# IOTPanel.net
KiCad netlist of a schematic drawn in EAGLE
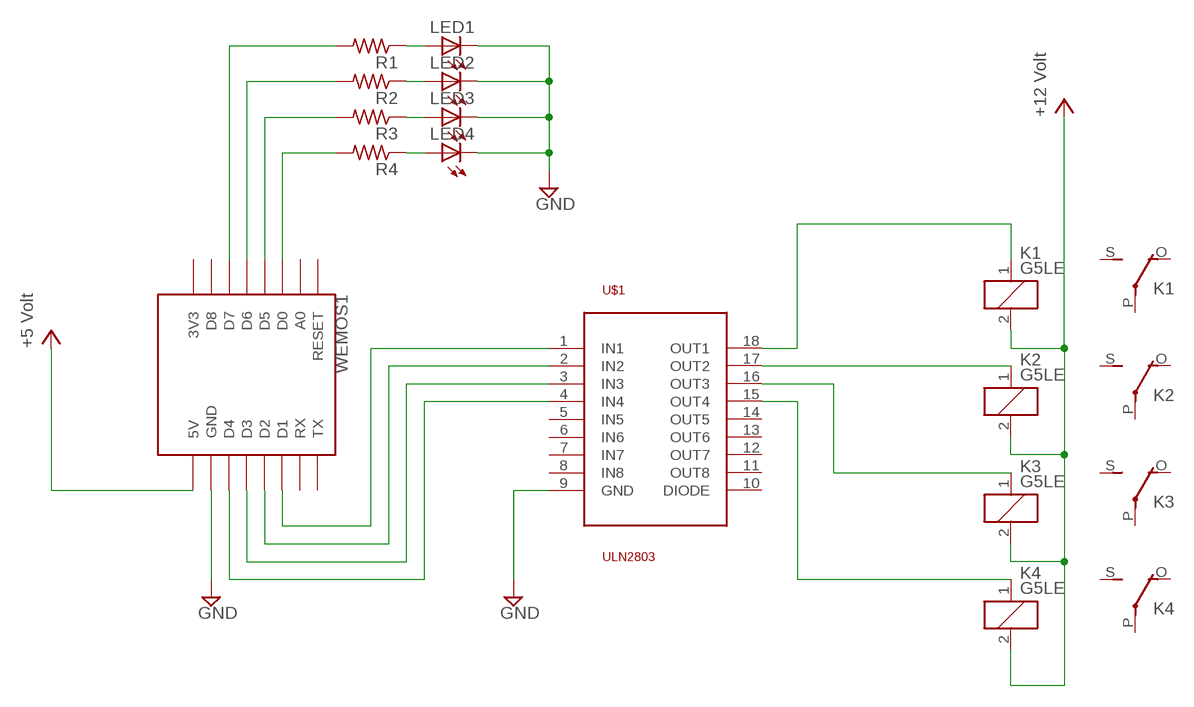
[diagram p0: schematic, sheet 1]

(export (version "E")
  (design (tool "Eeschema 10.0.6"))
  (components
    (comp (ref "K1")
      (value "G5LE")
      (footprint "eagle-import:G5LE")
      (libsource (lib "eagle-import") (part "G5LE"))
    )
    (comp (ref "K2")
      (value "G5LE")
      (footprint "eagle-import:G5LE")
      (libsource (lib "eagle-import") (part "G5LE"))
    )
    (comp (ref "K3")
      (value "G5LE")
      (footprint "eagle-import:G5LE")
      (libsource (lib "eagle-import") (part "G5LE"))
    )
    (comp (ref "K4")
      (value "G5LE")
      (footprint "eagle-import:G5LE")
      (libsource (lib "eagle-import") (part "G5LE"))
    )
    (comp (ref "LED1")
      (value "LED")
      (footprint "eagle-import:SMARTLED-TTW")
      (libsource (lib "eagle-import") (part "LED"))
    )
    (comp (ref "LED2")
      (value "LED")
      (footprint "eagle-import:SMARTLED-TTW")
      (libsource (lib "eagle-import") (part "LED"))
    )
    (comp (ref "LED3")
      (value "LED")
      (footprint "eagle-import:SMARTLED-TTW")
      (libsource (lib "eagle-import") (part "LED"))
    )
    (comp (ref "LED4")
      (value "LED")
      (footprint "eagle-import:SMARTLED-TTW")
      (libsource (lib "eagle-import") (part "LED"))
    )
    (comp (ref "R1")
      (value "R-US_0204/2V")
      (footprint "eagle-import:0204V")
      (libsource (lib "eagle-import") (part "R-US_0204/2V"))
    )
    (comp (ref "R2")
      (value "R-US_0204/2V")
      (footprint "eagle-import:0204V")
      (libsource (lib "eagle-import") (part "R-US_0204/2V"))
    )
    (comp (ref "R3")
      (value "R-US_0204/2V")
      (footprint "eagle-import:0204V")
      (libsource (lib "eagle-import") (part "R-US_0204/2V"))
    )
    (comp (ref "R4")
      (value "R-US_0204/2V")
      (footprint "eagle-import:0204V")
      (libsource (lib "eagle-import") (part "R-US_0204/2V"))
    )
    (comp (ref "U$1")
      (value "ULN2803")
      (footprint "eagle-import:SO18L")
      (libsource (lib "eagle-import") (part "ULN2803"))
    )
    (comp (ref "WEMOS1")
      (value "WEMOS-D1-MINI")
      (footprint "eagle-import:WEMOS-D1-MINI")
      (libsource (lib "eagle-import") (part "WEMOS-D1-MINI"))
    )
  )
  (nets
    (net (code "1") (name "+12 Volt") (class "Default")
      (node (ref "K1") (pin "2") (pinfunction "2_2") (pintype "passive"))
      (node (ref "K2") (pin "2") (pinfunction "2_2") (pintype "passive"))
      (node (ref "K3") (pin "2") (pinfunction "2_2") (pintype "passive"))
      (node (ref "K4") (pin "2") (pinfunction "2_2") (pintype "passive"))
      (node (ref "WEMOS1") (pin "5V") (pinfunction "5V_5V") (pintype "bidirectional"))
    )
    (net (code "2") (name "/DIODE") (class "Default")
      (node (ref "U$1") (pin "10") (pinfunction "DIODE_10") (pintype "power_in"))
    )
    (net (code "3") (name "GND") (class "Default")
      (node (ref "LED1") (pin "C@1") (pinfunction "C_C@1") (pintype "passive"))
      (node (ref "LED2") (pin "C@1") (pinfunction "C_C@1") (pintype "passive"))
      (node (ref "LED3") (pin "C@1") (pinfunction "C_C@1") (pintype "passive"))
      (node (ref "LED4") (pin "C@1") (pinfunction "C_C@1") (pintype "passive"))
      (node (ref "U$1") (pin "9") (pinfunction "GND_9") (pintype "power_in"))
      (node (ref "WEMOS1") (pin "GND") (pinfunction "GND_GND") (pintype "bidirectional"))
    )
    (net (code "4") (name "Net-(LED1-A)") (class "Default")
      (node (ref "LED1") (pin "A@1") (pinfunction "A_A@1") (pintype "passive"))
      (node (ref "R1") (pin "1") (pinfunction "1_1") (pintype "passive"))
    )
    (net (code "5") (name "Net-(LED2-A)") (class "Default")
      (node (ref "LED2") (pin "A@1") (pinfunction "A_A@1") (pintype "passive"))
      (node (ref "R2") (pin "1") (pinfunction "1_1") (pintype "passive"))
    )
    (net (code "6") (name "Net-(LED3-A)") (class "Default")
      (node (ref "LED3") (pin "A@1") (pinfunction "A_A@1") (pintype "passive"))
      (node (ref "R3") (pin "1") (pinfunction "1_1") (pintype "passive"))
    )
    (net (code "7") (name "Net-(LED4-A)") (class "Default")
      (node (ref "LED4") (pin "A@1") (pinfunction "A_A@1") (pintype "passive"))
      (node (ref "R4") (pin "1") (pinfunction "1_1") (pintype "passive"))
    )
    (net (code "8") (name "Net-(R1-Pad2)") (class "Default")
      (node (ref "R1") (pin "2") (pinfunction "2_2") (pintype "passive"))
      (node (ref "WEMOS1") (pin "D7") (pinfunction "D7_D7") (pintype "bidirectional"))
    )
    (net (code "9") (name "Net-(R2-Pad2)") (class "Default")
      (node (ref "R2") (pin "2") (pinfunction "2_2") (pintype "passive"))
      (node (ref "WEMOS1") (pin "D6") (pinfunction "D6_D6") (pintype "bidirectional"))
    )
    (net (code "10") (name "Net-(R3-Pad2)") (class "Default")
      (node (ref "R3") (pin "2") (pinfunction "2_2") (pintype "passive"))
      (node (ref "WEMOS1") (pin "D5") (pinfunction "D5_D5") (pintype "bidirectional"))
    )
    (net (code "11") (name "Net-(R4-Pad2)") (class "Default")
      (node (ref "R4") (pin "2") (pinfunction "2_2") (pintype "passive"))
      (node (ref "WEMOS1") (pin "D0") (pinfunction "D0_D0") (pintype "bidirectional"))
    )
    (net (code "12") (name "Net-(U$1-IN1)") (class "Default")
      (node (ref "U$1") (pin "1") (pinfunction "IN1_1") (pintype "input"))
      (node (ref "WEMOS1") (pin "D1") (pinfunction "D1_D1") (pintype "bidirectional"))
    )
    (net (code "13") (name "Net-(U$1-IN2)") (class "Default")
      (node (ref "U$1") (pin "2") (pinfunction "IN2_2") (pintype "input"))
      (node (ref "WEMOS1") (pin "D2") (pinfunction "D2_D2") (pintype "bidirectional"))
    )
    (net (code "14") (name "Net-(U$1-IN3)") (class "Default")
      (node (ref "U$1") (pin "3") (pinfunction "IN3_3") (pintype "input"))
      (node (ref "WEMOS1") (pin "D3") (pinfunction "D3_D3") (pintype "bidirectional"))
    )
    (net (code "15") (name "Net-(U$1-IN4)") (class "Default")
      (node (ref "U$1") (pin "4") (pinfunction "IN4_4") (pintype "input"))
      (node (ref "WEMOS1") (pin "D4") (pinfunction "D4_D4") (pintype "bidirectional"))
    )
    (net (code "16") (name "Net-(U$1-OUT1)") (class "Default")
      (node (ref "K1") (pin "1") (pinfunction "1_1") (pintype "passive"))
      (node (ref "U$1") (pin "18") (pinfunction "OUT1_18") (pintype "open_collector"))
    )
    (net (code "17") (name "Net-(U$1-OUT2)") (class "Default")
      (node (ref "K2") (pin "1") (pinfunction "1_1") (pintype "passive"))
      (node (ref "U$1") (pin "17") (pinfunction "OUT2_17") (pintype "open_collector"))
    )
    (net (code "18") (name "Net-(U$1-OUT3)") (class "Default")
      (node (ref "K3") (pin "1") (pinfunction "1_1") (pintype "passive"))
      (node (ref "U$1") (pin "16") (pinfunction "OUT3_16") (pintype "open_collector"))
    )
    (net (code "19") (name "Net-(U$1-OUT4)") (class "Default")
      (node (ref "K4") (pin "1") (pinfunction "1_1") (pintype "passive"))
      (node (ref "U$1") (pin "15") (pinfunction "OUT4_15") (pintype "open_collector"))
    )
    (net (code "20") (name "unconnected-(K1-PadO)") (class "Default")
      (node (ref "K1") (pin "O") (pinfunction "O_O") (pintype "passive"))
    )
    (net (code "21") (name "unconnected-(K1-PadP)") (class "Default")
      (node (ref "K1") (pin "P") (pinfunction "P_P") (pintype "passive"))
    )
    (net (code "22") (name "unconnected-(K1-PadS)") (class "Default")
      (node (ref "K1") (pin "S") (pinfunction "S_S") (pintype "passive"))
    )
    (net (code "23") (name "unconnected-(K2-PadO)") (class "Default")
      (node (ref "K2") (pin "O") (pinfunction "O_O") (pintype "passive"))
    )
    (net (code "24") (name "unconnected-(K2-PadP)") (class "Default")
      (node (ref "K2") (pin "P") (pinfunction "P_P") (pintype "passive"))
    )
    (net (code "25") (name "unconnected-(K2-PadS)") (class "Default")
      (node (ref "K2") (pin "S") (pinfunction "S_S") (pintype "passive"))
    )
    (net (code "26") (name "unconnected-(K3-PadO)") (class "Default")
      (node (ref "K3") (pin "O") (pinfunction "O_O") (pintype "passive"))
    )
    (net (code "27") (name "unconnected-(K3-PadP)") (class "Default")
      (node (ref "K3") (pin "P") (pinfunction "P_P") (pintype "passive"))
    )
    (net (code "28") (name "unconnected-(K3-PadS)") (class "Default")
      (node (ref "K3") (pin "S") (pinfunction "S_S") (pintype "passive"))
    )
    (net (code "29") (name "unconnected-(K4-PadO)") (class "Default")
      (node (ref "K4") (pin "O") (pinfunction "O_O") (pintype "passive"))
    )
    (net (code "30") (name "unconnected-(K4-PadP)") (class "Default")
      (node (ref "K4") (pin "P") (pinfunction "P_P") (pintype "passive"))
    )
    (net (code "31") (name "unconnected-(K4-PadS)") (class "Default")
      (node (ref "K4") (pin "S") (pinfunction "S_S") (pintype "passive"))
    )
    (net (code "32") (name "unconnected-(U$1-IN5-Pad5)") (class "Default")
      (node (ref "U$1") (pin "5") (pinfunction "IN5_5") (pintype "input"))
    )
    (net (code "33") (name "unconnected-(U$1-IN6-Pad6)") (class "Default")
      (node (ref "U$1") (pin "6") (pinfunction "IN6_6") (pintype "input"))
    )
    (net (code "34") (name "unconnected-(U$1-IN7-Pad7)") (class "Default")
      (node (ref "U$1") (pin "7") (pinfunction "IN7_7") (pintype "input"))
    )
    (net (code "35") (name "unconnected-(U$1-IN8-Pad8)") (class "Default")
      (node (ref "U$1") (pin "8") (pinfunction "IN8_8") (pintype "input"))
    )
    (net (code "36") (name "unconnected-(U$1-OUT5-Pad14)") (class "Default")
      (node (ref "U$1") (pin "14") (pinfunction "OUT5_14") (pintype "open_collector"))
    )
    (net (code "37") (name "unconnected-(U$1-OUT6-Pad13)") (class "Default")
      (node (ref "U$1") (pin "13") (pinfunction "OUT6_13") (pintype "open_collector"))
    )
    (net (code "38") (name "unconnected-(U$1-OUT7-Pad12)") (class "Default")
      (node (ref "U$1") (pin "12") (pinfunction "OUT7_12") (pintype "open_collector"))
    )
    (net (code "39") (name "unconnected-(U$1-OUT8-Pad11)") (class "Default")
      (node (ref "U$1") (pin "11") (pinfunction "OUT8_11") (pintype "open_collector"))
    )
    (net (code "40") (name "unconnected-(WEMOS1-Pad3V3)") (class "Default")
      (node (ref "WEMOS1") (pin "3V3") (pinfunction "3V3_3V3") (pintype "bidirectional"))
    )
    (net (code "41") (name "unconnected-(WEMOS1-PadA0)") (class "Default")
      (node (ref "WEMOS1") (pin "A0") (pinfunction "A0_A0") (pintype "bidirectional"))
    )
    (net (code "42") (name "unconnected-(WEMOS1-PadD8)") (class "Default")
      (node (ref "WEMOS1") (pin "D8") (pinfunction "D8_D8") (pintype "bidirectional"))
    )
    (net (code "43") (name "unconnected-(WEMOS1-PadRESET)") (class "Default")
      (node (ref "WEMOS1") (pin "RESET") (pinfunction "RESET_RESET") (pintype "bidirectional"))
    )
    (net (code "44") (name "unconnected-(WEMOS1-PadRX)") (class "Default")
      (node (ref "WEMOS1") (pin "RX") (pinfunction "RX_RX") (pintype "bidirectional"))
    )
    (net (code "45") (name "unconnected-(WEMOS1-PadTX)") (class "Default")
      (node (ref "WEMOS1") (pin "TX") (pinfunction "TX_TX") (pintype "bidirectional"))
    )
  )
)
